# Motor.net
KiCad netlist of a schematic drawn in Altium Designer
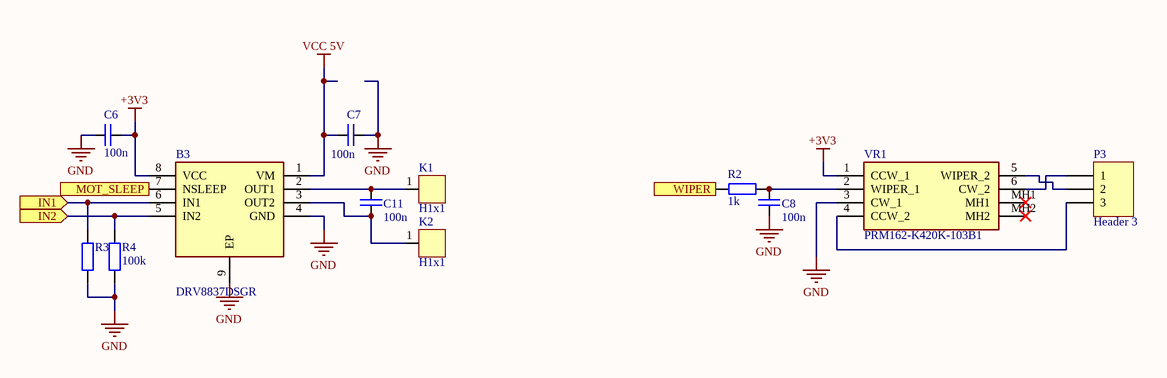
[diagram p0: Motor.SchDoc]

(export (version "E")
  (design (tool "Eeschema 10.0.6"))
  (components
    (comp (ref "B3")
      (value "DRV8837DSGR")
      (footprint "SON50P200X200X80-9N")
      (description "1.8A Low Voltage Brushed DC Motor Driver (PWM Ctrl)")
      (fields (field (name "MOUSER PART NUMBER") "595-DRV8837DSGR"))
      (libsource (lib "components_library") (part "DRV8837DSGR"))
    )
    (comp (ref "C6")
      (value "100n")
      (footprint "R1005_0402i_M")
      (description "Capacitor")
      (libsource (lib "General") (part "C"))
    )
    (comp (ref "C7")
      (value "100n")
      (footprint "R1005_0402i_M")
      (description "Capacitor")
      (libsource (lib "General") (part "C"))
    )
    (comp (ref "C8")
      (value "100n")
      (footprint "R1005_0402i_M")
      (description "Capacitor")
      (libsource (lib "General") (part "C"))
    )
    (comp (ref "C11")
      (value "100n")
      (footprint "R1005_0402i_M")
      (description "Capacitor")
      (libsource (lib "General") (part "C"))
    )
    (comp (ref "K1")
      (value "H1x1")
      (footprint "H1x1")
      (description "Header 1x1 (male)")
      (libsource (lib "Kon_Tipk") (part "H1x1"))
    )
    (comp (ref "K2")
      (value "H1x1")
      (footprint "H1x1")
      (description "Header 1x1 (male)")
      (libsource (lib "Kon_Tipk") (part "H1x1"))
    )
    (comp (ref "P3")
      (value "Header 3")
      (footprint "HDR1X3")
      (description "Header, 3-Pin")
      (fields (field (name "PUBLISHER") "Altium Limited"))
      (libsource (lib "Miscellaneous Connectors") (part "Header 3"))
    )
    (comp (ref "R2")
      (value "1k")
      (footprint "R1005_0402i_L")
      (description "R")
      (libsource (lib "General") (part "R"))
    )
    (comp (ref "R3")
      (value "100k")
      (footprint "R1005_0402i_L")
      (description "R")
      (libsource (lib "General") (part "R"))
    )
    (comp (ref "R4")
      (value "100k")
      (footprint "R1005_0402i_L")
      (description "R")
      (libsource (lib "General") (part "R"))
    )
    (comp (ref "VR1")
      (value "PRM162-K420K-103B1")
      (footprint "PRM162K415K103B1")
      (description "Variable Resistor")
      (fields (field (name "MOUSER PART NUMBER") "652-PRM162K420K103B1"))
      (libsource (lib "components_library") (part "PRM162-K420K-103B1"))
    )
  )
  (nets
    (net (code "1") (name "+3V3") (class "Default")
      (node (ref "B3") (pin "8") (pinfunction "VCC_8") (pintype "passive"))
      (node (ref "C6") (pin "2") (pinfunction "2_2") (pintype "passive"))
      (node (ref "VR1") (pin "1") (pinfunction "CCW_1_1") (pintype "passive"))
    )
    (net (code "2") (name "/IN1") (class "Default")
      (node (ref "B3") (pin "6") (pinfunction "IN1_6") (pintype "passive"))
      (node (ref "R3") (pin "1") (pintype "passive"))
    )
    (net (code "3") (name "/IN2") (class "Default")
      (node (ref "B3") (pin "5") (pinfunction "IN2_5") (pintype "passive"))
      (node (ref "R4") (pin "1") (pintype "passive"))
    )
    (net (code "4") (name "/MOT_SLEEP") (class "Default")
      (node (ref "B3") (pin "7") (pinfunction "NSLEEP_7") (pintype "passive"))
    )
    (net (code "5") (name "/WIPER") (class "Default") (node (ref "R2") (pin "1") (pintype "passive")))
    (net (code "6") (name "GND") (class "Default")
      (node (ref "B3") (pin "4") (pinfunction "GND_4") (pintype "passive"))
      (node (ref "B3") (pin "9") (pinfunction "EP_9") (pintype "passive"))
      (node (ref "C6") (pin "1") (pinfunction "1_1") (pintype "passive"))
      (node (ref "C7") (pin "2") (pinfunction "2_2") (pintype "passive"))
      (node (ref "C8") (pin "2") (pinfunction "2_2") (pintype "passive"))
      (node (ref "R3") (pin "2") (pintype "passive"))
      (node (ref "R4") (pin "2") (pintype "passive"))
      (node (ref "VR1") (pin "3") (pinfunction "CW_1_3") (pintype "passive"))
    )
    (net (code "7") (name "Net-(B3-OUT1)") (class "Default")
      (node (ref "B3") (pin "2") (pinfunction "OUT1_2") (pintype "passive"))
      (node (ref "C11") (pin "2") (pinfunction "2_2") (pintype "passive"))
      (node (ref "K1") (pin "1") (pinfunction "1_1") (pintype "passive"))
    )
    (net (code "8") (name "Net-(B3-OUT2)") (class "Default")
      (node (ref "B3") (pin "3") (pinfunction "OUT2_3") (pintype "passive"))
      (node (ref "C11") (pin "1") (pinfunction "1_1") (pintype "passive"))
      (node (ref "K2") (pin "1") (pinfunction "1_1") (pintype "passive"))
    )
    (net (code "9") (name "Net-(VR1-CCW_2)") (class "Default")
      (node (ref "P3") (pin "3") (pinfunction "3_3") (pintype "passive"))
      (node (ref "VR1") (pin "4") (pinfunction "CCW_2_4") (pintype "passive"))
    )
    (net (code "10") (name "Net-(VR1-CW_2)") (class "Default")
      (node (ref "P3") (pin "1") (pinfunction "1_1") (pintype "passive"))
      (node (ref "VR1") (pin "6") (pinfunction "CW_2_6") (pintype "passive"))
    )
    (net (code "11") (name "Net-(VR1-WIPER_1)") (class "Default")
      (node (ref "C8") (pin "1") (pinfunction "1_1") (pintype "passive"))
      (node (ref "R2") (pin "2") (pintype "passive"))
      (node (ref "VR1") (pin "2") (pinfunction "WIPER_1_2") (pintype "passive"))
    )
    (net (code "12") (name "Net-(VR1-WIPER_2)") (class "Default")
      (node (ref "P3") (pin "2") (pinfunction "2_2") (pintype "passive"))
      (node (ref "VR1") (pin "5") (pinfunction "WIPER_2_5") (pintype "passive"))
    )
    (net (code "13") (name "VCC 5V") (class "Default")
      (node (ref "B3") (pin "1") (pinfunction "VM_1") (pintype "passive"))
      (node (ref "C7") (pin "1") (pinfunction "1_1") (pintype "passive"))
    )
    (net (code "14") (name "unconnected-(VR1-PadMH1)") (class "Default")
      (node (ref "VR1") (pin "MH1") (pinfunction "MH1_MH1") (pintype "passive+no_connect"))
    )
    (net (code "15") (name "unconnected-(VR1-PadMH2)") (class "Default")
      (node (ref "VR1") (pin "MH2") (pinfunction "MH2_MH2") (pintype "passive+no_connect"))
    )
  )
)
